# Sheet3.net
KiCad netlist of a schematic drawn in Altium Designer
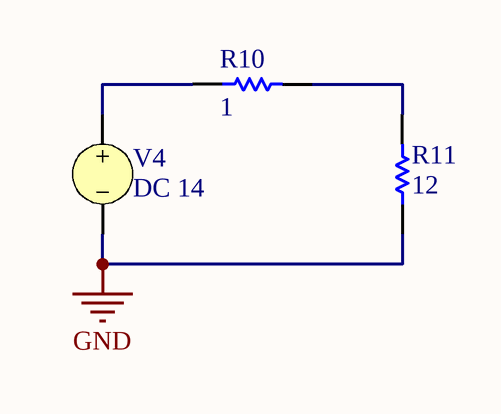
[diagram p0: Sheet3.SchDoc]

(export (version "E")
  (design (tool "Eeschema 10.0.6"))
  (components
    (comp (ref "R10")
      (value "1")
      (description "Resistor")
      (libsource (lib "Simulation Generic Components") (part "Resistor"))
    )
    (comp (ref "R11")
      (value "12")
      (description "Resistor")
      (libsource (lib "Simulation Generic Components") (part "Resistor"))
    )
    (comp (ref "V4")
      (value "DC 14")
      (description "Voltage Source")
      (fields (field (name "PUBLISHER") "Altium Limited"))
      (libsource (lib "Simulation Generic Components") (part "VSRC"))
    )
  )
  (nets
    (net (code "1") (name "GND") (class "Default")
      (node (ref "R11") (pin "1") (pinfunction "1_1") (pintype "passive"))
      (node (ref "V4") (pin "2") (pinfunction "2_2") (pintype "passive"))
    )
    (net (code "2") (name "Net-(R10-Pad1)") (class "Default")
      (node (ref "R10") (pin "1") (pinfunction "1_1") (pintype "passive"))
      (node (ref "V4") (pin "1") (pinfunction "1_1") (pintype "passive"))
    )
    (net (code "3") (name "Net-(R10-Pad2)") (class "Default")
      (node (ref "R10") (pin "2") (pinfunction "2_2") (pintype "passive"))
      (node (ref "R11") (pin "2") (pinfunction "2_2") (pintype "passive"))
    )
  )
)
